# ble112.net
KiCad netlist of a schematic drawn in EAGLE
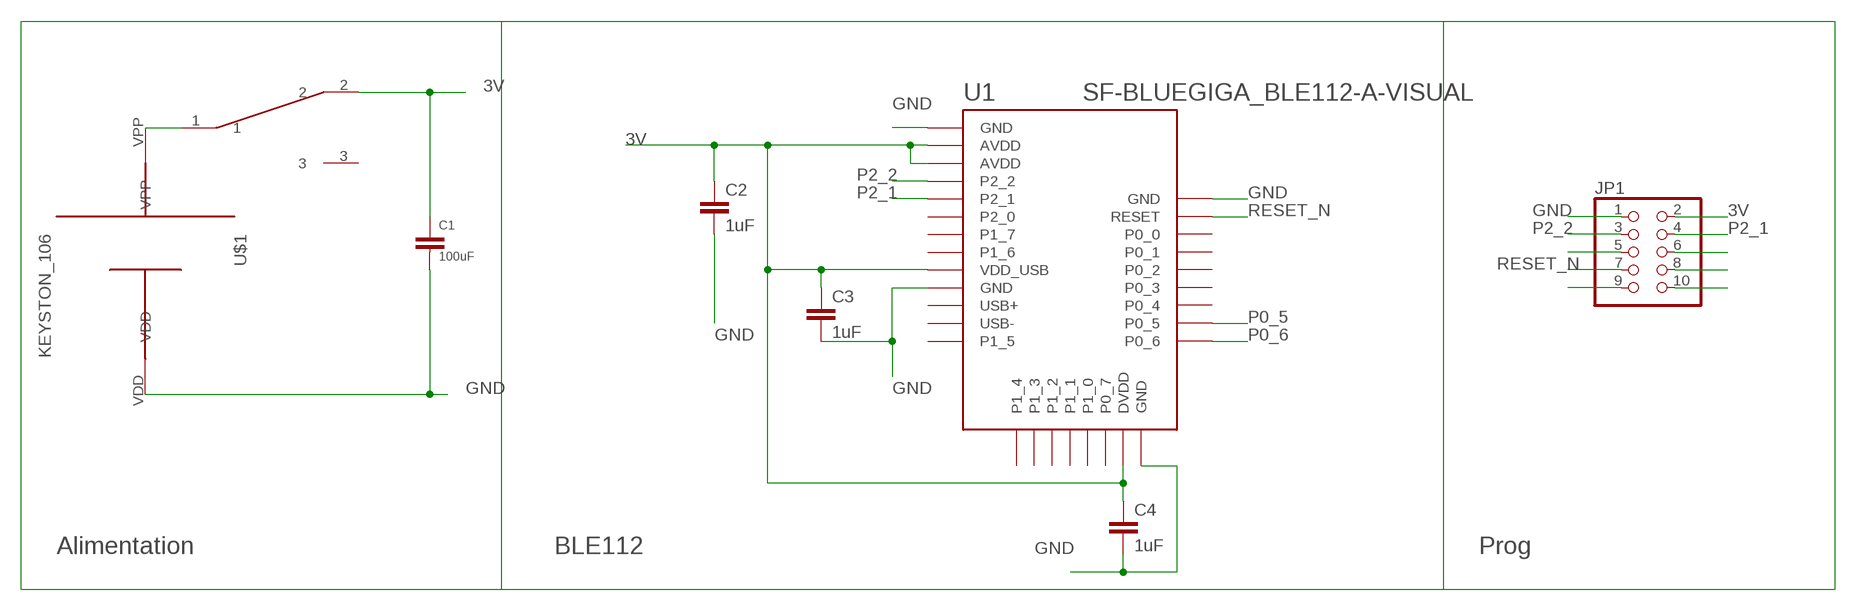
[diagram p0: schematic, sheet 1]

(export (version "E")
  (design (tool "Eeschema 10.0.6"))
  (components
    (comp (ref "C1")
      (value "100uF")
      (footprint "eagle-import:R1206")
      (libsource (lib "eagle-import") (part "C_1206"))
    )
    (comp (ref "C2")
      (value "1uF")
      (footprint "eagle-import:C1210")
      (libsource (lib "eagle-import") (part "C-EUC1210"))
    )
    (comp (ref "C3")
      (value "1uF")
      (footprint "eagle-import:C1210")
      (libsource (lib "eagle-import") (part "C-EUC1210"))
    )
    (comp (ref "C4")
      (value "1uF")
      (footprint "eagle-import:C1210")
      (libsource (lib "eagle-import") (part "C-EUC1210"))
    )
    (comp (ref "JP1")
      (value "PINHD-2X5")
      (footprint "eagle-import:2X05")
      (libsource (lib "eagle-import") (part "PINHD-2X5"))
    )
    (comp (ref "U$1")
      (value "KEYSTON_106")
      (footprint "eagle-import:CELL_HOLDER_PACKAGE")
      (libsource (lib "eagle-import") (part "KEYSTON_106"))
    )
    (comp (ref "U$2")
      (value "1K2")
      (footprint "eagle-import:1X03_90")
      (libsource (lib "eagle-import") (part "1K2"))
    )
    (comp (ref "U1")
      (value "SF-BLUEGIGA_BLE112-A-VISUAL")
      (footprint "eagle-import:SF-BLUEGIGA_BLE112-A")
      (libsource (lib "eagle-import") (part "SF-BLUEGIGA_BLE112-A-VISUAL"))
    )
  )
  (nets
    (net (code "1") (name "/3V") (class "Default")
      (node (ref "C1") (pin "1") (pinfunction "P$1_1") (pintype "passive"))
      (node (ref "C2") (pin "1") (pinfunction "1_1") (pintype "passive"))
      (node (ref "C3") (pin "1") (pinfunction "1_1") (pintype "passive"))
      (node (ref "C4") (pin "1") (pinfunction "1_1") (pintype "passive"))
      (node (ref "JP1") (pin "2") (pinfunction "2_2") (pintype "passive"))
      (node (ref "U$2") (pin "2") (pinfunction "2_2") (pintype "bidirectional"))
      (node (ref "U1") (pin "AVDD1") (pinfunction "AVDD_AVDD1") (pintype "power_in"))
      (node (ref "U1") (pin "AVDD2") (pinfunction "AVDD_AVDD2") (pintype "power_in"))
      (node (ref "U1") (pin "DVDD") (pinfunction "DVDD_DVDD") (pintype "power_in"))
      (node (ref "U1") (pin "VDD_USB") (pinfunction "VDD_USB_VDD_USB") (pintype "power_in"))
    )
    (net (code "2") (name "/GND") (class "Default")
      (node (ref "C1") (pin "2") (pinfunction "P$2_2") (pintype "passive"))
      (node (ref "C2") (pin "2") (pinfunction "2_2") (pintype "passive"))
      (node (ref "C3") (pin "2") (pinfunction "2_2") (pintype "passive"))
      (node (ref "C4") (pin "2") (pinfunction "2_2") (pintype "passive"))
      (node (ref "JP1") (pin "1") (pinfunction "1_1") (pintype "passive"))
      (node (ref "U$1") (pin "VDD") (pinfunction "VDD_VDD") (pintype "bidirectional"))
      (node (ref "U1") (pin "GND1") (pinfunction "GND_GND1") (pintype "power_in"))
      (node (ref "U1") (pin "GND2") (pinfunction "GND_GND2") (pintype "power_in"))
      (node (ref "U1") (pin "GND3") (pinfunction "GND_GND3") (pintype "power_in"))
      (node (ref "U1") (pin "GND4") (pinfunction "GND_GND4") (pintype "power_in"))
    )
    (net (code "3") (name "/P0_5") (class "Default")
      (node (ref "U1") (pin "P0_5") (pinfunction "P0_5_P0_5") (pintype "bidirectional"))
    )
    (net (code "4") (name "/P0_6") (class "Default")
      (node (ref "U1") (pin "P0_6") (pinfunction "P0_6_P0_6") (pintype "bidirectional"))
    )
    (net (code "5") (name "/P2_1") (class "Default")
      (node (ref "JP1") (pin "4") (pinfunction "4_4") (pintype "passive"))
      (node (ref "U1") (pin "P2_1") (pinfunction "P2_1_P2_1") (pintype "bidirectional"))
    )
    (net (code "6") (name "/P2_2") (class "Default")
      (node (ref "JP1") (pin "3") (pinfunction "3_3") (pintype "passive"))
      (node (ref "U1") (pin "P2_2") (pinfunction "P2_2_P2_2") (pintype "bidirectional"))
    )
    (net (code "7") (name "/RESET_N") (class "Default")
      (node (ref "JP1") (pin "7") (pinfunction "7_7") (pintype "passive"))
      (node (ref "U1") (pin "RESET") (pinfunction "RESET_RESET") (pintype "input"))
    )
    (net (code "8") (name "Net-(U$1-PadVPP)") (class "Default")
      (node (ref "U$1") (pin "VPP") (pinfunction "VPP_VPP") (pintype "bidirectional"))
      (node (ref "U$2") (pin "1") (pinfunction "1_1") (pintype "bidirectional"))
    )
    (net (code "9") (name "unconnected-(JP1-Pad5)") (class "Default")
      (node (ref "JP1") (pin "5") (pinfunction "5_5") (pintype "passive"))
    )
    (net (code "10") (name "unconnected-(JP1-Pad6)") (class "Default")
      (node (ref "JP1") (pin "6") (pinfunction "6_6") (pintype "passive"))
    )
    (net (code "11") (name "unconnected-(JP1-Pad8)") (class "Default")
      (node (ref "JP1") (pin "8") (pinfunction "8_8") (pintype "passive"))
    )
    (net (code "12") (name "unconnected-(JP1-Pad9)") (class "Default")
      (node (ref "JP1") (pin "9") (pinfunction "9_9") (pintype "passive"))
    )
    (net (code "13") (name "unconnected-(JP1-Pad10)") (class "Default")
      (node (ref "JP1") (pin "10") (pinfunction "10_10") (pintype "passive"))
    )
    (net (code "14") (name "unconnected-(U$2-Pad3)") (class "Default")
      (node (ref "U$2") (pin "3") (pinfunction "3_3") (pintype "bidirectional"))
    )
    (net (code "15") (name "unconnected-(U1-PadP0_0)") (class "Default")
      (node (ref "U1") (pin "P0_0") (pinfunction "P0_0_P0_0") (pintype "bidirectional"))
    )
    (net (code "16") (name "unconnected-(U1-PadP0_1)") (class "Default")
      (node (ref "U1") (pin "P0_1") (pinfunction "P0_1_P0_1") (pintype "bidirectional"))
    )
    (net (code "17") (name "unconnected-(U1-PadP0_2)") (class "Default")
      (node (ref "U1") (pin "P0_2") (pinfunction "P0_2_P0_2") (pintype "bidirectional"))
    )
    (net (code "18") (name "unconnected-(U1-PadP0_3)") (class "Default")
      (node (ref "U1") (pin "P0_3") (pinfunction "P0_3_P0_3") (pintype "bidirectional"))
    )
    (net (code "19") (name "unconnected-(U1-PadP0_4)") (class "Default")
      (node (ref "U1") (pin "P0_4") (pinfunction "P0_4_P0_4") (pintype "bidirectional"))
    )
    (net (code "20") (name "unconnected-(U1-PadP0_7)") (class "Default")
      (node (ref "U1") (pin "P0_7") (pinfunction "P0_7_P0_7") (pintype "bidirectional"))
    )
    (net (code "21") (name "unconnected-(U1-PadP1_0)") (class "Default")
      (node (ref "U1") (pin "P1_0") (pinfunction "P1_0_P1_0") (pintype "bidirectional"))
    )
    (net (code "22") (name "unconnected-(U1-PadP1_1)") (class "Default")
      (node (ref "U1") (pin "P1_1") (pinfunction "P1_1_P1_1") (pintype "bidirectional"))
    )
    (net (code "23") (name "unconnected-(U1-PadP1_2)") (class "Default")
      (node (ref "U1") (pin "P1_2") (pinfunction "P1_2_P1_2") (pintype "bidirectional"))
    )
    (net (code "24") (name "unconnected-(U1-PadP1_3)") (class "Default")
      (node (ref "U1") (pin "P1_3") (pinfunction "P1_3_P1_3") (pintype "bidirectional"))
    )
    (net (code "25") (name "unconnected-(U1-PadP1_4)") (class "Default")
      (node (ref "U1") (pin "P1_4") (pinfunction "P1_4_P1_4") (pintype "bidirectional"))
    )
    (net (code "26") (name "unconnected-(U1-PadP1_5)") (class "Default")
      (node (ref "U1") (pin "P1_5") (pinfunction "P1_5_P1_5") (pintype "bidirectional"))
    )
    (net (code "27") (name "unconnected-(U1-PadP1_6)") (class "Default")
      (node (ref "U1") (pin "P1_6") (pinfunction "P1_6_P1_6") (pintype "bidirectional"))
    )
    (net (code "28") (name "unconnected-(U1-PadP1_7)") (class "Default")
      (node (ref "U1") (pin "P1_7") (pinfunction "P1_7_P1_7") (pintype "bidirectional"))
    )
    (net (code "29") (name "unconnected-(U1-PadP2_0)") (class "Default")
      (node (ref "U1") (pin "P2_0") (pinfunction "P2_0_P2_0") (pintype "bidirectional"))
    )
    (net (code "30") (name "unconnected-(U1-PadUSB+)") (class "Default")
      (node (ref "U1") (pin "USB+") (pinfunction "USB+_USB+") (pintype "bidirectional"))
    )
    (net (code "31") (name "unconnected-(U1-PadUSB-)") (class "Default")
      (node (ref "U1") (pin "USB-") (pinfunction "USB-_USB-") (pintype "bidirectional"))
    )
  )
)
